# Yukari_4_Copernicus_11DoF.net
KiCad netlist of a schematic drawn in EAGLE
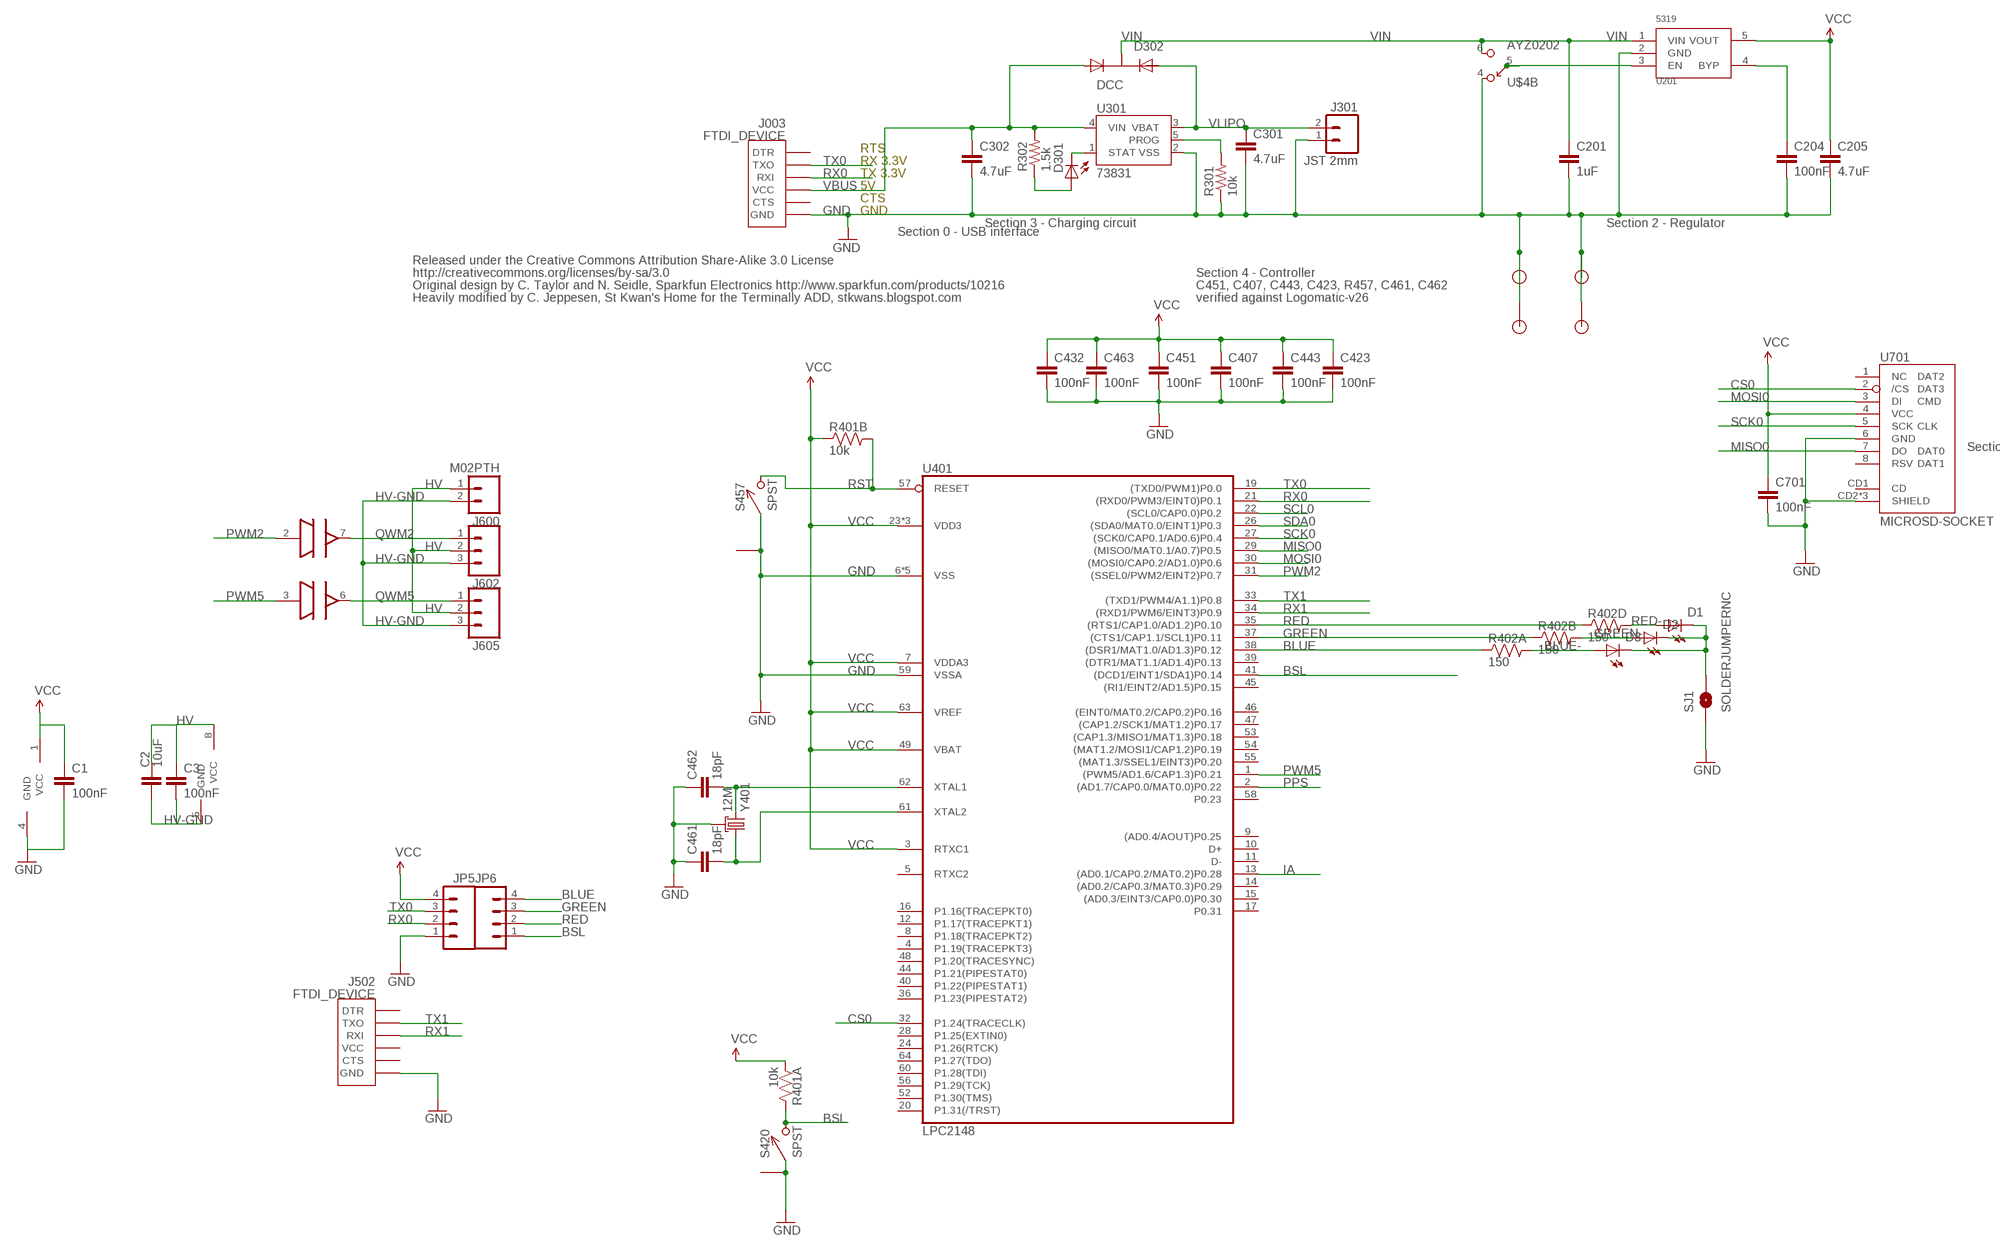
[diagram p0: schematic, sheet 1, part 1 of 2]
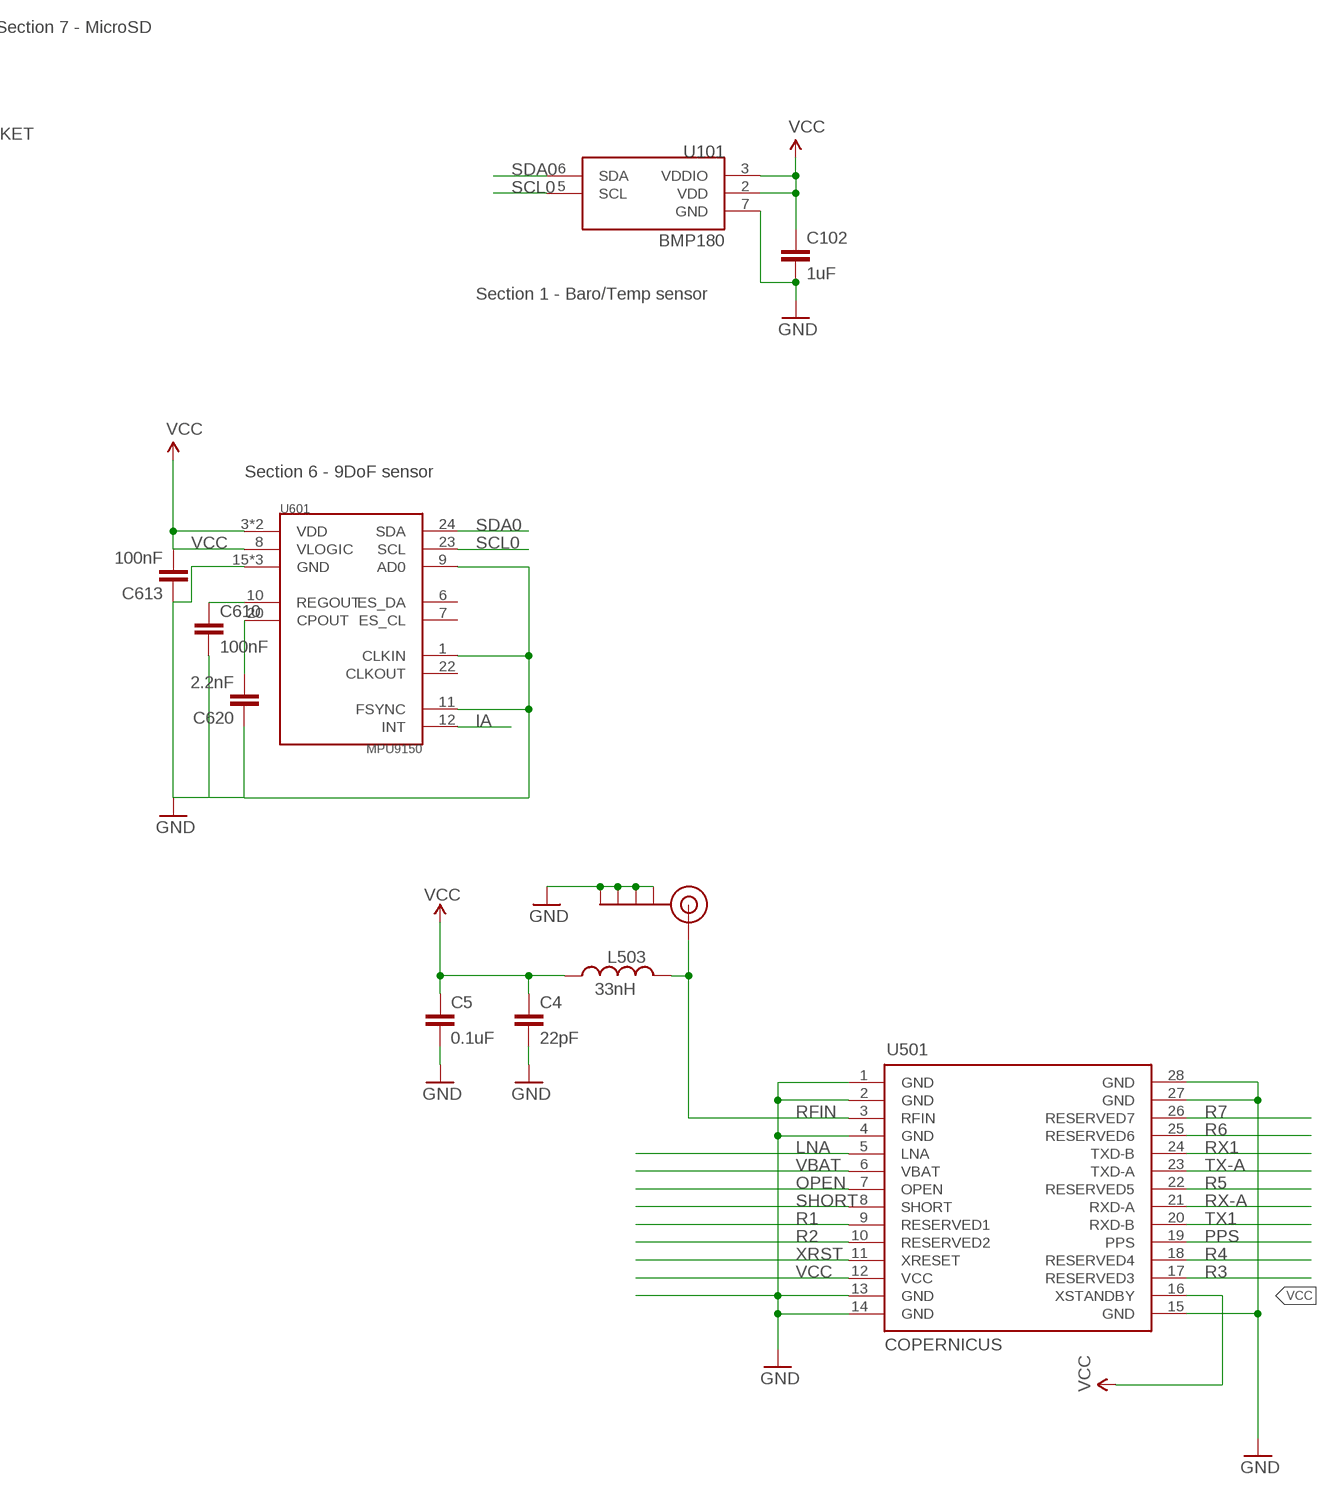
[diagram p1: schematic, sheet 1, part 2 of 2]

(export (version "E")
  (design (tool "Eeschema 10.0.6"))
  (components
    (comp (ref "C1")
      (value "100nF")
      (footprint "eagle-import:0402-CAP")
      (libsource (lib "eagle-import") (part "CAP0402-CAP"))
    )
    (comp (ref "C2")
      (value "10uF")
      (footprint "eagle-import:0603-CAP")
      (libsource (lib "eagle-import") (part "CAP0603-CAP"))
    )
    (comp (ref "C3")
      (value "100nF")
      (footprint "eagle-import:0402-CAP")
      (libsource (lib "eagle-import") (part "CAP0402-CAP"))
    )
    (comp (ref "C4")
      (value "22pF")
      (footprint "eagle-import:0603-CAP")
      (libsource (lib "eagle-import") (part "SparkFun-Passives_CAP0603-CAP"))
    )
    (comp (ref "C5")
      (value "0.1uF")
      (footprint "eagle-import:0603-CAP")
      (libsource (lib "eagle-import") (part "SparkFun-Passives_CAP0603-CAP"))
    )
    (comp (ref "C102")
      (value "1uF")
      (footprint "eagle-import:0402-CAP")
      (libsource (lib "eagle-import") (part "SparkFun-Passives_CAP0402-CAP"))
    )
    (comp (ref "C201")
      (value "1uF")
      (footprint "eagle-import:0402-CAP")
      (libsource (lib "eagle-import") (part "CAP0402-CAP"))
    )
    (comp (ref "C204")
      (value "100nF")
      (footprint "eagle-import:0402-CAP")
      (libsource (lib "eagle-import") (part "CAP0402-CAP"))
    )
    (comp (ref "C205")
      (value "4.7uF")
      (footprint "eagle-import:0402-CAP")
      (libsource (lib "eagle-import") (part "CAP0402-CAP"))
    )
    (comp (ref "C301")
      (value "4.7uF")
      (footprint "eagle-import:0402-CAP")
      (libsource (lib "eagle-import") (part "CAP0402-CAP"))
    )
    (comp (ref "C302")
      (value "4.7uF")
      (footprint "eagle-import:0402-CAP")
      (libsource (lib "eagle-import") (part "CAP0402-CAP"))
    )
    (comp (ref "C407")
      (value "100nF")
      (footprint "eagle-import:0402-CAP")
      (libsource (lib "eagle-import") (part "CAP0402-CAP"))
    )
    (comp (ref "C423")
      (value "100nF")
      (footprint "eagle-import:0402-CAP")
      (libsource (lib "eagle-import") (part "CAP0402-CAP"))
    )
    (comp (ref "C432")
      (value "100nF")
      (footprint "eagle-import:0402-CAP")
      (libsource (lib "eagle-import") (part "CAP0402-CAP"))
    )
    (comp (ref "C443")
      (value "100nF")
      (footprint "eagle-import:0402-CAP")
      (libsource (lib "eagle-import") (part "CAP0402-CAP"))
    )
    (comp (ref "C451")
      (value "100nF")
      (footprint "eagle-import:0402-CAP")
      (libsource (lib "eagle-import") (part "CAP0402-CAP"))
    )
    (comp (ref "C461")
      (value "18pF")
      (footprint "eagle-import:0402-CAP")
      (libsource (lib "eagle-import") (part "CAP0402-CAP"))
    )
    (comp (ref "C462")
      (value "18pF")
      (footprint "eagle-import:0402-CAP")
      (libsource (lib "eagle-import") (part "CAP0402-CAP"))
    )
    (comp (ref "C463")
      (value "100nF")
      (footprint "eagle-import:0402-CAP")
      (libsource (lib "eagle-import") (part "CAP0402-CAP"))
    )
    (comp (ref "C610")
      (value "100nF")
      (footprint "eagle-import:0402-CAP")
      (libsource (lib "eagle-import") (part "SparkFun-Passives_CAP0402-CAP"))
    )
    (comp (ref "C613")
      (value "100nF")
      (footprint "eagle-import:0402-CAP")
      (libsource (lib "eagle-import") (part "SparkFun-Passives_CAP0402-CAP"))
    )
    (comp (ref "C620")
      (value "2.2nF")
      (footprint "eagle-import:0402-CAP")
      (libsource (lib "eagle-import") (part "SparkFun-Passives_CAP0402-CAP"))
    )
    (comp (ref "C701")
      (value "100nF")
      (footprint "eagle-import:0402-CAP")
      (libsource (lib "eagle-import") (part "CAP0402-CAP"))
    )
    (comp (ref "D1")
      (value "RED")
      (footprint "eagle-import:LED-0603")
      (libsource (lib "eagle-import") (part "LED0603"))
    )
    (comp (ref "D2")
      (value "GREEN")
      (footprint "eagle-import:LED-0603")
      (libsource (lib "eagle-import") (part "LED0603"))
    )
    (comp (ref "D3")
      (value "BLUE")
      (footprint "eagle-import:LED-0603")
      (libsource (lib "eagle-import") (part "LED0603"))
    )
    (comp (ref "D301")
      (value "RED")
      (footprint "eagle-import:LED-0603")
      (libsource (lib "eagle-import") (part "LED0603"))
    )
    (comp (ref "D302")
      (value "DCC")
      (footprint "eagle-import:SOT-23-3")
      (libsource (lib "eagle-import") (part "PMEG2005CT"))
    )
    (comp (ref "J003")
      (value "FTDI_DEVICE")
      (footprint "eagle-import:FTDI_DEVICE_SIDE")
      (libsource (lib "eagle-import") (part "FTDI_DEVICE"))
    )
    (comp (ref "J301")
      (value "JST 2mm")
      (footprint "eagle-import:JST-2-SMD")
      (libsource (lib "eagle-import") (part "M02-JST-2MM-SMT"))
    )
    (comp (ref "J502")
      (value "FTDI_DEVICE")
      (footprint "eagle-import:FTDI_DEVICE_SIDE")
      (libsource (lib "eagle-import") (part "FTDI_DEVICE"))
    )
    (comp (ref "J600")
      (value "M02PTH")
      (footprint "eagle-import:1X02")
      (libsource (lib "eagle-import") (part "SparkFun-Connectors_M02PTH"))
    )
    (comp (ref "J602")
      (value "M03PTH")
      (footprint "eagle-import:1X03")
      (libsource (lib "eagle-import") (part "M03PTH"))
    )
    (comp (ref "J605")
      (value "M03PTH")
      (footprint "eagle-import:1X03")
      (libsource (lib "eagle-import") (part "M03PTH"))
    )
    (comp (ref "JP1")
      (value "STANDOFF")
      (footprint "eagle-import:STANDOFF")
      (libsource (lib "eagle-import") (part "STANDOFF"))
    )
    (comp (ref "JP2")
      (value "STANDOFF")
      (footprint "eagle-import:STANDOFF")
      (libsource (lib "eagle-import") (part "STANDOFF"))
    )
    (comp (ref "JP3")
      (value "STANDOFF")
      (footprint "eagle-import:STANDOFF")
      (libsource (lib "eagle-import") (part "STANDOFF"))
    )
    (comp (ref "JP4")
      (value "STANDOFF")
      (footprint "eagle-import:STANDOFF")
      (libsource (lib "eagle-import") (part "STANDOFF"))
    )
    (comp (ref "JP5")
      (value "M04PTH")
      (footprint "eagle-import:1X04")
      (libsource (lib "eagle-import") (part "M04PTH"))
    )
    (comp (ref "JP6")
      (value "M04PTH")
      (footprint "eagle-import:1X04")
      (libsource (lib "eagle-import") (part "M04PTH"))
    )
    (comp (ref "JP7")
      (value "SMA_EDGE")
      (footprint "eagle-import:SMA_EDGE")
      (libsource (lib "eagle-import") (part "SMA_EDGE"))
    )
    (comp (ref "L503")
      (value "33nH")
      (footprint "eagle-import:0603")
      (libsource (lib "eagle-import") (part "INDUCTOR0603"))
    )
    (comp (ref "R301")
      (value "10k")
      (footprint "eagle-import:0402-RES")
      (libsource (lib "eagle-import") (part "RESISTOR0402-RES"))
    )
    (comp (ref "R302")
      (value "1.5k")
      (footprint "eagle-import:0402-RES")
      (libsource (lib "eagle-import") (part "RESISTOR0402-RES"))
    )
    (comp (ref "R401")
      (value "10k")
      (footprint "eagle-import:CRA02")
      (libsource (lib "eagle-import") (part "RP2EXB24V"))
    )
    (comp (ref "R402")
      (value "150")
      (footprint "eagle-import:CRA04")
      (libsource (lib "eagle-import") (part "RP404"))
    )
    (comp (ref "S420")
      (value "SPST")
      (footprint "eagle-import:B3U-1100P")
      (libsource (lib "eagle-import") (part "B3U-1100P"))
    )
    (comp (ref "S457")
      (value "SPST")
      (footprint "eagle-import:B3U-1100P")
      (libsource (lib "eagle-import") (part "B3U-1100P"))
    )
    (comp (ref "SJ1")
      (value "SOLDERJUMPERNC")
      (footprint "eagle-import:SJ_2S")
      (libsource (lib "eagle-import") (part "SOLDERJUMPERNC"))
    )
    (comp (ref "U$4")
      (value "AYZ0202")
      (footprint "eagle-import:AYZ0202")
      (libsource (lib "eagle-import") (part "AYZ0202"))
    )
    (comp (ref "U101")
      (value "BMP180")
      (footprint "eagle-import:BMP180")
      (libsource (lib "eagle-import") (part "BMP180"))
    )
    (comp (ref "U201")
      (value "5319")
      (footprint "eagle-import:SOT-23-5")
      (libsource (lib "eagle-import") (part "MIC5319D5"))
    )
    (comp (ref "U301")
      (value "73831")
      (footprint "eagle-import:SOT23-5")
      (libsource (lib "eagle-import") (part "MCP73831"))
    )
    (comp (ref "U401")
      (value "LPC2148")
      (footprint "eagle-import:LQFP64")
      (libsource (lib "eagle-import") (part "LPC2148"))
    )
    (comp (ref "U501")
      (value "COPERNICUS")
      (footprint "eagle-import:COPERNICUS")
      (libsource (lib "eagle-import") (part "COPERNICUSSMD"))
    )
    (comp (ref "U600")
      (value "ADUM3221")
      (footprint "eagle-import:SO8N")
      (libsource (lib "eagle-import") (part "ADUM3221"))
    )
    (comp (ref "U601")
      (value "MPU9150")
      (footprint "eagle-import:LLGA24")
      (libsource (lib "eagle-import") (part "MPU9150"))
    )
    (comp (ref "U701")
      (value "MICROSD-SOCKET")
      (footprint "eagle-import:MICROSD-SOCKET-PP")
      (libsource (lib "eagle-import") (part "MICROSD-SOCKET"))
    )
    (comp (ref "Y401")
      (value "12M")
      (footprint "eagle-import:CRYSTAL_SMD")
      (libsource (lib "eagle-import") (part "TSX-3225"))
    )
  )
  (nets
    (net (code "1") (name "/BLUE") (class "Default")
      (node (ref "JP6") (pin "4") (pinfunction "4_4") (pintype "passive"))
      (node (ref "R402") (pin "1") (pinfunction "1_1") (pintype "passive"))
      (node (ref "U401") (pin "38") (pinfunction "(DSR1/MAT1.0/AD1.3)P0.12_38") (pintype "bidirectional"))
    )
    (net (code "2") (name "/BLUE-") (class "Default")
      (node (ref "D3") (pin "A") (pinfunction "A_A") (pintype "passive"))
      (node (ref "R402") (pin "8") (pinfunction "2_8") (pintype "passive"))
    )
    (net (code "3") (name "/BSL") (class "Default")
      (node (ref "JP6") (pin "1") (pinfunction "1_1") (pintype "passive"))
      (node (ref "R401") (pin "4") (pinfunction "2_4") (pintype "passive"))
      (node (ref "S420") (pin "P$2") (pinfunction "2_P$2") (pintype "bidirectional"))
      (node (ref "U401") (pin "41") (pinfunction "(DCD1/EINT1/SDA1)P0.14_41") (pintype "bidirectional"))
    )
    (net (code "4") (name "/CS0") (class "Default")
      (node (ref "U401") (pin "32") (pinfunction "P1.24(TRACECLK)_32") (pintype "bidirectional"))
      (node (ref "U701") (pin "2") (pinfunction "/CS_2") (pintype "bidirectional"))
    )
    (net (code "5") (name "/GREEN") (class "Default")
      (node (ref "JP6") (pin "3") (pinfunction "3_3") (pintype "passive"))
      (node (ref "R402") (pin "2") (pinfunction "1_2") (pintype "passive"))
      (node (ref "U401") (pin "37") (pinfunction "(CTS1/CAP1.1/SCL1)P0.11_37") (pintype "bidirectional"))
    )
    (net (code "6") (name "/GREEN-") (class "Default")
      (node (ref "D2") (pin "A") (pinfunction "A_A") (pintype "passive"))
      (node (ref "R402") (pin "7") (pinfunction "2_7") (pintype "passive"))
    )
    (net (code "7") (name "/HV") (class "Default")
      (node (ref "C2") (pin "1") (pinfunction "1_1") (pintype "passive"))
      (node (ref "C3") (pin "1") (pinfunction "1_1") (pintype "passive"))
      (node (ref "J600") (pin "1") (pinfunction "1_1") (pintype "passive"))
      (node (ref "J602") (pin "2") (pinfunction "2_2") (pintype "passive"))
      (node (ref "J605") (pin "2") (pinfunction "2_2") (pintype "passive"))
      (node (ref "U600") (pin "8") (pinfunction "VCC_8") (pintype "bidirectional"))
    )
    (net (code "8") (name "/HV-GND") (class "Default")
      (node (ref "C2") (pin "2") (pinfunction "2_2") (pintype "passive"))
      (node (ref "C3") (pin "2") (pinfunction "2_2") (pintype "passive"))
      (node (ref "J600") (pin "2") (pinfunction "2_2") (pintype "passive"))
      (node (ref "J602") (pin "3") (pinfunction "3_3") (pintype "passive"))
      (node (ref "J605") (pin "3") (pinfunction "3_3") (pintype "passive"))
      (node (ref "U600") (pin "5") (pinfunction "GND_5") (pintype "bidirectional"))
    )
    (net (code "9") (name "/IA") (class "Default")
      (node (ref "U401") (pin "13") (pinfunction "(AD0.1/CAP0.2/MAT0.2)P0.28_13") (pintype "bidirectional"))
      (node (ref "U601") (pin "12") (pinfunction "INT_12") (pintype "bidirectional"))
    )
    (net (code "10") (name "/LNA") (class "Default")
      (node (ref "U501") (pin "5") (pinfunction "LNA_5") (pintype "bidirectional"))
    )
    (net (code "11") (name "/MISO0") (class "Default")
      (node (ref "U401") (pin "29") (pinfunction "(MISO0/MAT0.1/A0.7)P0.5_29") (pintype "bidirectional"))
      (node (ref "U701") (pin "7") (pinfunction "DO_7") (pintype "bidirectional"))
    )
    (net (code "12") (name "/MOSI0") (class "Default")
      (node (ref "U401") (pin "30") (pinfunction "(MOSI0/CAP0.2/AD1.0)P0.6_30") (pintype "bidirectional"))
      (node (ref "U701") (pin "3") (pinfunction "DI_3") (pintype "bidirectional"))
    )
    (net (code "13") (name "/OPEN") (class "Default")
      (node (ref "U501") (pin "7") (pinfunction "OPEN_7") (pintype "bidirectional"))
    )
    (net (code "14") (name "/PPS") (class "Default")
      (node (ref "U401") (pin "2") (pinfunction "(AD1.7/CAP0.0/MAT0.0)P0.22_2") (pintype "bidirectional"))
      (node (ref "U501") (pin "19") (pinfunction "PPS_19") (pintype "bidirectional"))
    )
    (net (code "15") (name "/PWM2") (class "Default")
      (node (ref "U401") (pin "31") (pinfunction "(SSEL0/PWM2/EINT2)P0.7_31") (pintype "bidirectional"))
      (node (ref "U600") (pin "2") (pinfunction "IN_2") (pintype "input"))
    )
    (net (code "16") (name "/PWM5") (class "Default")
      (node (ref "U401") (pin "1") (pinfunction "(PWM5/AD1.6/CAP1.3)P0.21_1") (pintype "bidirectional"))
      (node (ref "U600") (pin "3") (pinfunction "IN_3") (pintype "input"))
    )
    (net (code "17") (name "/QWM2") (class "Default")
      (node (ref "J602") (pin "1") (pinfunction "1_1") (pintype "passive"))
      (node (ref "U600") (pin "7") (pinfunction "OUT_7") (pintype "bidirectional"))
    )
    (net (code "18") (name "/QWM5") (class "Default")
      (node (ref "J605") (pin "1") (pinfunction "1_1") (pintype "passive"))
      (node (ref "U600") (pin "6") (pinfunction "OUT_6") (pintype "bidirectional"))
    )
    (net (code "19") (name "/R1") (class "Default")
      (node (ref "U501") (pin "9") (pinfunction "RESERVED1_9") (pintype "bidirectional"))
    )
    (net (code "20") (name "/R2") (class "Default")
      (node (ref "U501") (pin "10") (pinfunction "RESERVED2_10") (pintype "bidirectional"))
    )
    (net (code "21") (name "/R3") (class "Default")
      (node (ref "U501") (pin "17") (pinfunction "RESERVED3_17") (pintype "bidirectional"))
    )
    (net (code "22") (name "/R4") (class "Default")
      (node (ref "U501") (pin "18") (pinfunction "RESERVED4_18") (pintype "bidirectional"))
    )
    (net (code "23") (name "/R5") (class "Default")
      (node (ref "U501") (pin "22") (pinfunction "RESERVED5_22") (pintype "bidirectional"))
    )
    (net (code "24") (name "/R6") (class "Default")
      (node (ref "U501") (pin "25") (pinfunction "RESERVED6_25") (pintype "bidirectional"))
    )
    (net (code "25") (name "/R7") (class "Default")
      (node (ref "U501") (pin "26") (pinfunction "RESERVED7_26") (pintype "bidirectional"))
    )
    (net (code "26") (name "/RED") (class "Default")
      (node (ref "JP6") (pin "2") (pinfunction "2_2") (pintype "passive"))
      (node (ref "R402") (pin "4") (pinfunction "1_4") (pintype "passive"))
      (node (ref "U401") (pin "35") (pinfunction "(RTS1/CAP1.0/AD1.2)P0.10_35") (pintype "bidirectional"))
    )
    (net (code "27") (name "/RED-") (class "Default")
      (node (ref "D1") (pin "A") (pinfunction "A_A") (pintype "passive"))
      (node (ref "R402") (pin "5") (pinfunction "2_5") (pintype "passive"))
    )
    (net (code "28") (name "/RFIN") (class "Default")
      (node (ref "JP7") (pin "SIG") (pinfunction "SIGNAL_SIG") (pintype "bidirectional"))
      (node (ref "L503") (pin "2") (pinfunction "2_2") (pintype "passive"))
      (node (ref "U501") (pin "3") (pinfunction "RFIN_3") (pintype "bidirectional"))
    )
    (net (code "29") (name "/RST") (class "Default")
      (node (ref "R401") (pin "3") (pinfunction "2_3") (pintype "passive"))
      (node (ref "S457") (pin "P$2") (pinfunction "2_P$2") (pintype "bidirectional"))
      (node (ref "U401") (pin "57") (pinfunction "RESET_57") (pintype "input"))
    )
    (net (code "30") (name "/RX-A") (class "Default")
      (node (ref "U501") (pin "21") (pinfunction "RXD-A_21") (pintype "bidirectional"))
    )
    (net (code "31") (name "/RX0") (class "Default")
      (node (ref "J003") (pin "P$3") (pinfunction "RXI_P$3") (pintype "bidirectional"))
      (node (ref "JP5") (pin "2") (pinfunction "2_2") (pintype "passive"))
      (node (ref "U401") (pin "21") (pinfunction "(RXD0/PWM3/EINT0)P0.1_21") (pintype "bidirectional"))
    )
    (net (code "32") (name "/RX1") (class "Default")
      (node (ref "J502") (pin "P$3") (pinfunction "RXI_P$3") (pintype "bidirectional"))
      (node (ref "U401") (pin "34") (pinfunction "(RXD1/PWM6/EINT3)P0.9_34") (pintype "bidirectional"))
      (node (ref "U501") (pin "24") (pinfunction "TXD-B_24") (pintype "bidirectional"))
    )
    (net (code "33") (name "/SCK0") (class "Default")
      (node (ref "U401") (pin "27") (pinfunction "(SCK0/CAP0.1/AD0.6)P0.4_27") (pintype "bidirectional"))
      (node (ref "U701") (pin "5") (pinfunction "SCK_5") (pintype "bidirectional"))
    )
    (net (code "34") (name "/SCL0") (class "Default")
      (node (ref "U101") (pin "5") (pinfunction "SCL_5") (pintype "input"))
      (node (ref "U401") (pin "22") (pinfunction "(SCL0/CAP0.0)P0.2_22") (pintype "bidirectional"))
      (node (ref "U601") (pin "23") (pinfunction "SCL_23") (pintype "bidirectional"))
    )
    (net (code "35") (name "/SDA0") (class "Default")
      (node (ref "U101") (pin "6") (pinfunction "SDA_6") (pintype "bidirectional"))
      (node (ref "U401") (pin "26") (pinfunction "(SDA0/MAT0.0/EINT1)P0.3_26") (pintype "bidirectional"))
      (node (ref "U601") (pin "24") (pinfunction "SDA_24") (pintype "bidirectional"))
    )
    (net (code "36") (name "/SHORT") (class "Default")
      (node (ref "U501") (pin "8") (pinfunction "SHORT_8") (pintype "bidirectional"))
    )
    (net (code "37") (name "/TX-A") (class "Default")
      (node (ref "U501") (pin "23") (pinfunction "TXD-A_23") (pintype "bidirectional"))
    )
    (net (code "38") (name "/TX0") (class "Default")
      (node (ref "J003") (pin "P$2") (pinfunction "TXO_P$2") (pintype "bidirectional"))
      (node (ref "JP5") (pin "3") (pinfunction "3_3") (pintype "passive"))
      (node (ref "U401") (pin "19") (pinfunction "(TXD0/PWM1)P0.0_19") (pintype "bidirectional"))
    )
    (net (code "39") (name "/TX1") (class "Default")
      (node (ref "J502") (pin "P$2") (pinfunction "TXO_P$2") (pintype "bidirectional"))
      (node (ref "U401") (pin "33") (pinfunction "(TXD1/PWM4/A1.1)P0.8_33") (pintype "bidirectional"))
      (node (ref "U501") (pin "20") (pinfunction "RXD-B_20") (pintype "bidirectional"))
    )
    (net (code "40") (name "/VBAT") (class "Default")
      (node (ref "U501") (pin "6") (pinfunction "VBAT_6") (pintype "bidirectional"))
    )
    (net (code "41") (name "/VBUS") (class "Default")
      (node (ref "C302") (pin "1") (pinfunction "1_1") (pintype "passive"))
      (node (ref "D302") (pin "1") (pinfunction "A1_1") (pintype "passive"))
      (node (ref "J003") (pin "P$4") (pinfunction "VCC_P$4") (pintype "bidirectional"))
      (node (ref "R302") (pin "2") (pinfunction "2_2") (pintype "passive"))
      (node (ref "U301") (pin "4") (pinfunction "VIN_4") (pintype "power_in"))
    )
    (net (code "42") (name "/VIN") (class "Default")
      (node (ref "C201") (pin "1") (pinfunction "1_1") (pintype "passive"))
      (node (ref "D302") (pin "3") (pinfunction "K_3") (pintype "passive"))
      (node (ref "U$4") (pin "6") (pinfunction "P$2_6") (pintype "bidirectional"))
      (node (ref "U201") (pin "1") (pinfunction "VIN_1") (pintype "bidirectional"))
    )
    (net (code "43") (name "/VLIPO") (class "Default")
      (node (ref "C301") (pin "1") (pinfunction "1_1") (pintype "passive"))
      (node (ref "D302") (pin "2") (pinfunction "A2_2") (pintype "passive"))
      (node (ref "J301") (pin "2") (pinfunction "2_2") (pintype "passive"))
      (node (ref "U301") (pin "3") (pinfunction "VBAT_3") (pintype "power_in"))
    )
    (net (code "44") (name "/XRST") (class "Default")
      (node (ref "U501") (pin "11") (pinfunction "XRESET_11") (pintype "bidirectional"))
    )
    (net (code "45") (name "GND") (class "Default")
      (node (ref "C1") (pin "2") (pinfunction "2_2") (pintype "passive"))
      (node (ref "C102") (pin "2") (pinfunction "2_2") (pintype "passive"))
      (node (ref "C201") (pin "2") (pinfunction "2_2") (pintype "passive"))
      (node (ref "C204") (pin "2") (pinfunction "2_2") (pintype "passive"))
      (node (ref "C205") (pin "2") (pinfunction "2_2") (pintype "passive"))
      (node (ref "C301") (pin "2") (pinfunction "2_2") (pintype "passive"))
      (node (ref "C302") (pin "2") (pinfunction "2_2") (pintype "passive"))
      (node (ref "C4") (pin "2") (pinfunction "2_2") (pintype "passive"))
      (node (ref "C407") (pin "2") (pinfunction "2_2") (pintype "passive"))
      (node (ref "C423") (pin "2") (pinfunction "2_2") (pintype "passive"))
      (node (ref "C432") (pin "2") (pinfunction "2_2") (pintype "passive"))
      (node (ref "C443") (pin "2") (pinfunction "2_2") (pintype "passive"))
      (node (ref "C451") (pin "2") (pinfunction "2_2") (pintype "passive"))
      (node (ref "C461") (pin "1") (pinfunction "1_1") (pintype "passive"))
      (node (ref "C462") (pin "1") (pinfunction "1_1") (pintype "passive"))
      (node (ref "C463") (pin "2") (pinfunction "2_2") (pintype "passive"))
      (node (ref "C5") (pin "2") (pinfunction "2_2") (pintype "passive"))
      (node (ref "C610") (pin "2") (pinfunction "2_2") (pintype "passive"))
      (node (ref "C613") (pin "1") (pinfunction "1_1") (pintype "passive"))
      (node (ref "C620") (pin "1") (pinfunction "1_1") (pintype "passive"))
      (node (ref "C701") (pin "2") (pinfunction "2_2") (pintype "passive"))
      (node (ref "J003") (pin "P$6") (pinfunction "GND_P$6") (pintype "bidirectional"))
      (node (ref "J301") (pin "1") (pinfunction "1_1") (pintype "passive"))
      (node (ref "J502") (pin "P$6") (pinfunction "GND_P$6") (pintype "bidirectional"))
      (node (ref "JP1") (pin "P$1") (pinfunction "P$1_P$1") (pintype "bidirectional"))
      (node (ref "JP2") (pin "P$1") (pinfunction "P$1_P$1") (pintype "bidirectional"))
      (node (ref "JP3") (pin "P$1") (pinfunction "P$1_P$1") (pintype "bidirectional"))
      (node (ref "JP4") (pin "P$1") (pinfunction "P$1_P$1") (pintype "bidirectional"))
      (node (ref "JP5") (pin "1") (pinfunction "1_1") (pintype "passive"))
      (node (ref "JP7") (pin "GND@0") (pinfunction "GND_GND@0") (pintype "bidirectional"))
      (node (ref "JP7") (pin "GND@1") (pinfunction "GND_GND@1") (pintype "bidirectional"))
      (node (ref "JP7") (pin "GND@2") (pinfunction "GND_GND@2") (pintype "bidirectional"))
      (node (ref "JP7") (pin "GND@3") (pinfunction "GND_GND@3") (pintype "bidirectional"))
      (node (ref "R301") (pin "1") (pinfunction "1_1") (pintype "passive"))
      (node (ref "S420") (pin "P$1") (pinfunction "1_P$1") (pintype "bidirectional"))
      (node (ref "S420") (pin "P$3") (pinfunction "1_P$3") (pintype "bidirectional"))
      (node (ref "S457") (pin "P$1") (pinfunction "1_P$1") (pintype "bidirectional"))
      (node (ref "S457") (pin "P$3") (pinfunction "1_P$3") (pintype "bidirectional"))
      (node (ref "SJ1") (pin "1") (pinfunction "1_1") (pintype "passive"))
      (node (ref "U$4") (pin "4") (pinfunction "P$1_4") (pintype "bidirectional"))
      (node (ref "U101") (pin "7") (pinfunction "GND_7") (pintype "power_in"))
      (node (ref "U201") (pin "2") (pinfunction "GND_2") (pintype "bidirectional"))
      (node (ref "U301") (pin "2") (pinfunction "VSS_2") (pintype "power_in"))
      (node (ref "U401") (pin "18") (pinfunction "VSS_18") (pintype "power_in"))
      (node (ref "U401") (pin "25") (pinfunction "VSS_25") (pintype "power_in"))
      (node (ref "U401") (pin "42") (pinfunction "VSS_42") (pintype "power_in"))
      (node (ref "U401") (pin "50") (pinfunction "VSS_50") (pintype "power_in"))
      (node (ref "U401") (pin "59") (pinfunction "VSSA_59") (pintype "power_in"))
      (node (ref "U401") (pin "6") (pinfunction "VSS_6") (pintype "power_in"))
      (node (ref "U501") (pin "1") (pinfunction "GND_1") (pintype "bidirectional"))
      (node (ref "U501") (pin "13") (pinfunction "GND_13") (pintype "bidirectional"))
      (node (ref "U501") (pin "14") (pinfunction "GND_14") (pintype "bidirectional"))
      (node (ref "U501") (pin "15") (pinfunction "GND_15") (pintype "bidirectional"))
      (node (ref "U501") (pin "2") (pinfunction "GND_2") (pintype "bidirectional"))
      (node (ref "U501") (pin "27") (pinfunction "GND_27") (pintype "bidirectional"))
      (node (ref "U501") (pin "28") (pinfunction "GND_28") (pintype "bidirectional"))
      (node (ref "U501") (pin "4") (pinfunction "GND_4") (pintype "bidirectional"))
      (node (ref "U600") (pin "4") (pinfunction "GND_4") (pintype "bidirectional"))
      (node (ref "U601") (pin "1") (pinfunction "CLKIN_1") (pintype "bidirectional"))
      (node (ref "U601") (pin "11") (pinfunction "FSYNC_11") (pintype "bidirectional"))
      (node (ref "U601") (pin "15") (pinfunction "GND_15") (pintype "bidirectional"))
      (node (ref "U601") (pin "17") (pinfunction "GND_17") (pintype "bidirectional"))
      (node (ref "U601") (pin "18") (pinfunction "GND_18") (pintype "bidirectional"))
      (node (ref "U601") (pin "9") (pinfunction "AD0_9") (pintype "bidirectional"))
      (node (ref "U701") (pin "6") (pinfunction "GND_6") (pintype "bidirectional"))
      (node (ref "U701") (pin "CD2") (pinfunction "SHIELD_CD2") (pintype "bidirectional"))
      (node (ref "U701") (pin "GND1") (pinfunction "SHIELD_GND1") (pintype "bidirectional"))
      (node (ref "U701") (pin "GND3") (pinfunction "SHIELD_GND3") (pintype "bidirectional"))
      (node (ref "Y401") (pin "2") (pinfunction "GND_2") (pintype "passive"))
      (node (ref "Y401") (pin "4") (pinfunction "GND_4") (pintype "passive"))
    )
    (net (code "46") (name "Net-(D1-PadC)") (class "Default")
      (node (ref "D1") (pin "C") (pinfunction "C_C") (pintype "passive"))
      (node (ref "D2") (pin "C") (pinfunction "C_C") (pintype "passive"))
      (node (ref "D3") (pin "C") (pinfunction "C_C") (pintype "passive"))
      (node (ref "SJ1") (pin "2") (pinfunction "2_2") (pintype "passive"))
    )
    (net (code "47") (name "Net-(D301-PadA)") (class "Default")
      (node (ref "D301") (pin "A") (pinfunction "A_A") (pintype "passive"))
      (node (ref "R302") (pin "1") (pinfunction "1_1") (pintype "passive"))
    )
    (net (code "48") (name "Net-(U$4B-P$3)") (class "Default")
      (node (ref "U$4") (pin "5") (pinfunction "P$3_5") (pintype "bidirectional"))
      (node (ref "U201") (pin "3") (pinfunction "EN_3") (pintype "bidirectional"))
    )
    (net (code "49") (name "Net-(U201-BYP)") (class "Default")
      (node (ref "C204") (pin "1") (pinfunction "1_1") (pintype "passive"))
      (node (ref "U201") (pin "4") (pinfunction "BYP_4") (pintype "bidirectional"))
    )
    (net (code "50") (name "Net-(U301-PROG)") (class "Default")
      (node (ref "R301") (pin "2") (pinfunction "2_2") (pintype "passive"))
      (node (ref "U301") (pin "5") (pinfunction "PROG_5") (pintype "input"))
    )
    (net (code "51") (name "Net-(U301-STAT)") (class "Default")
      (node (ref "D301") (pin "C") (pinfunction "C_C") (pintype "passive"))
      (node (ref "U301") (pin "1") (pinfunction "STAT_1") (pintype "output"))
    )
    (net (code "52") (name "Net-(U401-XTAL1)") (class "Default")
      (node (ref "C462") (pin "2") (pinfunction "2_2") (pintype "passive"))
      (node (ref "U401") (pin "62") (pinfunction "XTAL1_62") (pintype "input"))
      (node (ref "Y401") (pin "3") (pinfunction "2_3") (pintype "passive"))
    )
    (net (code "53") (name "Net-(U401-XTAL2)") (class "Default")
      (node (ref "C461") (pin "2") (pinfunction "2_2") (pintype "passive"))
      (node (ref "U401") (pin "61") (pinfunction "XTAL2_61") (pintype "output"))
      (node (ref "Y401") (pin "1") (pinfunction "1_1") (pintype "passive"))
    )
    (net (code "54") (name "Net-(U601-CPOUT)") (class "Default")
      (node (ref "C620") (pin "2") (pinfunction "2_2") (pintype "passive"))
      (node (ref "U601") (pin "20") (pinfunction "CPOUT_20") (pintype "bidirectional"))
    )
    (net (code "55") (name "Net-(U601-REGOUT)") (class "Default")
      (node (ref "C610") (pin "1") (pinfunction "1_1") (pintype "passive"))
      (node (ref "U601") (pin "10") (pinfunction "REGOUT_10") (pintype "bidirectional"))
    )
    (net (code "56") (name "VCC") (class "Default")
      (node (ref "C1") (pin "1") (pinfunction "1_1") (pintype "passive"))
      (node (ref "C102") (pin "1") (pinfunction "1_1") (pintype "passive"))
      (node (ref "C205") (pin "1") (pinfunction "1_1") (pintype "passive"))
      (node (ref "C4") (pin "1") (pinfunction "1_1") (pintype "passive"))
      (node (ref "C407") (pin "1") (pinfunction "1_1") (pintype "passive"))
      (node (ref "C423") (pin "1") (pinfunction "1_1") (pintype "passive"))
      (node (ref "C432") (pin "1") (pinfunction "1_1") (pintype "passive"))
      (node (ref "C443") (pin "1") (pinfunction "1_1") (pintype "passive"))
      (node (ref "C451") (pin "1") (pinfunction "1_1") (pintype "passive"))
      (node (ref "C463") (pin "1") (pinfunction "1_1") (pintype "passive"))
      (node (ref "C5") (pin "1") (pinfunction "1_1") (pintype "passive"))
      (node (ref "C613") (pin "2") (pinfunction "2_2") (pintype "passive"))
      (node (ref "C701") (pin "1") (pinfunction "1_1") (pintype "passive"))
      (node (ref "JP5") (pin "4") (pinfunction "4_4") (pintype "passive"))
      (node (ref "L503") (pin "1") (pinfunction "1_1") (pintype "passive"))
      (node (ref "R401") (pin "1") (pinfunction "1_1") (pintype "passive"))
      (node (ref "R401") (pin "2") (pinfunction "1_2") (pintype "passive"))
      (node (ref "U101") (pin "2") (pinfunction "VDD_2") (pintype "power_in"))
      (node (ref "U101") (pin "3") (pinfunction "VDDIO_3") (pintype "power_in"))
      (node (ref "U201") (pin "5") (pinfunction "VOUT_5") (pintype "bidirectional"))
      (node (ref "U401") (pin "23") (pinfunction "VDD3_23") (pintype "power_in"))
      (node (ref "U401") (pin "3") (pinfunction "RTXC1_3") (pintype "input"))
      (node (ref "U401") (pin "43") (pinfunction "VDD3_43") (pintype "power_in"))
      (node (ref "U401") (pin "49") (pinfunction "VBAT_49") (pintype "power_in"))
      (node (ref "U401") (pin "51") (pinfunction "VDD3_51") (pintype "power_in"))
      (node (ref "U401") (pin "63") (pinfunction "VREF_63") (pintype "input"))
      (node (ref "U401") (pin "7") (pinfunction "VDDA3_7") (pintype "power_in"))
      (node (ref "U501") (pin "12") (pinfunction "VCC_12") (pintype "bidirectional"))
      (node (ref "U501") (pin "16") (pinfunction "XSTANDBY_16") (pintype "bidirectional"))
      (node (ref "U600") (pin "1") (pinfunction "VCC_1") (pintype "bidirectional"))
      (node (ref "U601") (pin "13") (pinfunction "VDD_13") (pintype "bidirectional"))
      (node (ref "U601") (pin "3") (pinfunction "VDD_3") (pintype "bidirectional"))
      (node (ref "U601") (pin "8") (pinfunction "VLOGIC_8") (pintype "bidirectional"))
      (node (ref "U701") (pin "4") (pinfunction "VCC_4") (pintype "bidirectional"))
    )
    (net (code "57") (name "unconnected-(J003-CTS-PadP$5)") (class "Default")
      (node (ref "J003") (pin "P$5") (pinfunction "CTS_P$5") (pintype "bidirectional"))
    )
    (net (code "58") (name "unconnected-(J003-DTR-PadP$1)") (class "Default")
      (node (ref "J003") (pin "P$1") (pinfunction "DTR_P$1") (pintype "bidirectional"))
    )
    (net (code "59") (name "unconnected-(J502-CTS-PadP$5)") (class "Default")
      (node (ref "J502") (pin "P$5") (pinfunction "CTS_P$5") (pintype "bidirectional"))
    )
    (net (code "60") (name "unconnected-(J502-DTR-PadP$1)") (class "Default")
      (node (ref "J502") (pin "P$1") (pinfunction "DTR_P$1") (pintype "bidirectional"))
    )
    (net (code "61") (name "unconnected-(J502-VCC-PadP$4)") (class "Default")
      (node (ref "J502") (pin "P$4") (pinfunction "VCC_P$4") (pintype "bidirectional"))
    )
    (net (code "62") (name "unconnected-(U401-(AD0.2{slash}CAP0.3{slash}MAT0.3)P0.29-Pad14)") (class "Default")
      (node (ref "U401") (pin "14") (pinfunction "(AD0.2/CAP0.3/MAT0.3)P0.29_14") (pintype "bidirectional"))
    )
    (net (code "63") (name "unconnected-(U401-(AD0.3{slash}EINT3{slash}CAP0.0)P0.30-Pad15)") (class "Default")
      (node (ref "U401") (pin "15") (pinfunction "(AD0.3/EINT3/CAP0.0)P0.30_15") (pintype "bidirectional"))
    )
    (net (code "64") (name "unconnected-(U401-(AD0.4{slash}AOUT)P0.25-Pad9)") (class "Default")
      (node (ref "U401") (pin "9") (pinfunction "(AD0.4/AOUT)P0.25_9") (pintype "bidirectional"))
    )
    (net (code "65") (name "unconnected-(U401-(CAP1.2{slash}SCK1{slash}MAT1.2)P0.17-Pad47)") (class "Default")
      (node (ref "U401") (pin "47") (pinfunction "(CAP1.2/SCK1/MAT1.2)P0.17_47") (pintype "bidirectional"))
    )
    (net (code "66") (name "unconnected-(U401-(CAP1.3{slash}MISO1{slash}MAT1.3)P0.18-Pad53)") (class "Default")
      (node (ref "U401") (pin "53") (pinfunction "(CAP1.3/MISO1/MAT1.3)P0.18_53") (pintype "bidirectional"))
    )
    (net (code "67") (name "unconnected-(U401-(DTR1{slash}MAT1.1{slash}AD1.4)P0.13-Pad39)") (class "Default")
      (node (ref "U401") (pin "39") (pinfunction "(DTR1/MAT1.1/AD1.4)P0.13_39") (pintype "bidirectional"))
    )
    (net (code "68") (name "unconnected-(U401-(EINT0{slash}MAT0.2{slash}CAP0.2)P0.16-Pad46)") (class "Default")
      (node (ref "U401") (pin "46") (pinfunction "(EINT0/MAT0.2/CAP0.2)P0.16_46") (pintype "bidirectional"))
    )
    (net (code "69") (name "unconnected-(U401-(MAT1.2{slash}MOSI1{slash}CAP1.2)P0.19-Pad54)") (class "Default")
      (node (ref "U401") (pin "54") (pinfunction "(MAT1.2/MOSI1/CAP1.2)P0.19_54") (pintype "bidirectional"))
    )
    (net (code "70") (name "unconnected-(U401-(MAT1.3{slash}SSEL1{slash}EINT3)P0.20-Pad55)") (class "Default")
      (node (ref "U401") (pin "55") (pinfunction "(MAT1.3/SSEL1/EINT3)P0.20_55") (pintype "bidirectional"))
    )
    (net (code "71") (name "unconnected-(U401-(RI1{slash}EINT2{slash}AD1.5)P0.15-Pad45)") (class "Default")
      (node (ref "U401") (pin "45") (pinfunction "(RI1/EINT2/AD1.5)P0.15_45") (pintype "bidirectional"))
    )
    (net (code "72") (name "unconnected-(U401-D+-Pad10)") (class "Default")
      (node (ref "U401") (pin "10") (pinfunction "D+_10") (pintype "bidirectional"))
    )
    (net (code "73") (name "unconnected-(U401-D--Pad11)") (class "Default")
      (node (ref "U401") (pin "11") (pinfunction "D-_11") (pintype "bidirectional"))
    )
    (net (code "74") (name "unconnected-(U401-P0.23-Pad58)") (class "Default")
      (node (ref "U401") (pin "58") (pinfunction "P0.23_58") (pintype "bidirectional"))
    )
    (net (code "75") (name "unconnected-(U401-P0.31-Pad17)") (class "Default")
      (node (ref "U401") (pin "17") (pinfunction "P0.31_17") (pintype "output"))
    )
    (net (code "76") (name "unconnected-(U401-P1.16(TRACEPKT0)-Pad16)") (class "Default")
      (node (ref "U401") (pin "16") (pinfunction "P1.16(TRACEPKT0)_16") (pintype "bidirectional"))
    )
    (net (code "77") (name "unconnected-(U401-P1.17(TRACEPKT1)-Pad12)") (class "Default")
      (node (ref "U401") (pin "12") (pinfunction "P1.17(TRACEPKT1)_12") (pintype "bidirectional"))
    )
    (net (code "78") (name "unconnected-(U401-P1.18(TRACEPKT2)-Pad8)") (class "Default")
      (node (ref "U401") (pin "8") (pinfunction "P1.18(TRACEPKT2)_8") (pintype "bidirectional"))
    )
    (net (code "79") (name "unconnected-(U401-P1.19(TRACEPKT3)-Pad4)") (class "Default")
      (node (ref "U401") (pin "4") (pinfunction "P1.19(TRACEPKT3)_4") (pintype "bidirectional"))
    )
    (net (code "80") (name "unconnected-(U401-P1.20(TRACESYNC)-Pad48)") (class "Default")
      (node (ref "U401") (pin "48") (pinfunction "P1.20(TRACESYNC)_48") (pintype "bidirectional"))
    )
    (net (code "81") (name "unconnected-(U401-P1.21(PIPESTAT0)-Pad44)") (class "Default")
      (node (ref "U401") (pin "44") (pinfunction "P1.21(PIPESTAT0)_44") (pintype "bidirectional"))
    )
    (net (code "82") (name "unconnected-(U401-P1.22(PIPESTAT1)-Pad40)") (class "Default")
      (node (ref "U401") (pin "40") (pinfunction "P1.22(PIPESTAT1)_40") (pintype "bidirectional"))
    )
    (net (code "83") (name "unconnected-(U401-P1.23(PIPESTAT2)-Pad36)") (class "Default")
      (node (ref "U401") (pin "36") (pinfunction "P1.23(PIPESTAT2)_36") (pintype "bidirectional"))
    )
    (net (code "84") (name "unconnected-(U401-P1.25(EXTIN0)-Pad28)") (class "Default")
      (node (ref "U401") (pin "28") (pinfunction "P1.25(EXTIN0)_28") (pintype "bidirectional"))
    )
    (net (code "85") (name "unconnected-(U401-P1.26(RTCK)-Pad24)") (class "Default")
      (node (ref "U401") (pin "24") (pinfunction "P1.26(RTCK)_24") (pintype "bidirectional"))
    )
    (net (code "86") (name "unconnected-(U401-P1.27(TDO)-Pad64)") (class "Default")
      (node (ref "U401") (pin "64") (pinfunction "P1.27(TDO)_64") (pintype "bidirectional"))
    )
    (net (code "87") (name "unconnected-(U401-P1.28(TDI)-Pad60)") (class "Default")
      (node (ref "U401") (pin "60") (pinfunction "P1.28(TDI)_60") (pintype "bidirectional"))
    )
    (net (code "88") (name "unconnected-(U401-P1.29(TCK)-Pad56)") (class "Default")
      (node (ref "U401") (pin "56") (pinfunction "P1.29(TCK)_56") (pintype "bidirectional"))
    )
    (net (code "89") (name "unconnected-(U401-P1.30(TMS)-Pad52)") (class "Default")
      (node (ref "U401") (pin "52") (pinfunction "P1.30(TMS)_52") (pintype "bidirectional"))
    )
    (net (code "90") (name "unconnected-(U401-P1.31({slash}TRST)-Pad20)") (class "Default")
      (node (ref "U401") (pin "20") (pinfunction "P1.31(/TRST)_20") (pintype "bidirectional"))
    )
    (net (code "91") (name "unconnected-(U401-RTXC2-Pad5)") (class "Default")
      (node (ref "U401") (pin "5") (pinfunction "RTXC2_5") (pintype "output"))
    )
    (net (code "92") (name "unconnected-(U601-CLKOUT-Pad22)") (class "Default")
      (node (ref "U601") (pin "22") (pinfunction "CLKOUT_22") (pintype "bidirectional"))
    )
    (net (code "93") (name "unconnected-(U601-ES_CL-Pad7)") (class "Default")
      (node (ref "U601") (pin "7") (pinfunction "ES_CL_7") (pintype "bidirectional"))
    )
    (net (code "94") (name "unconnected-(U601-ES_DA-Pad6)") (class "Default")
      (node (ref "U601") (pin "6") (pinfunction "ES_DA_6") (pintype "bidirectional"))
    )
    (net (code "95") (name "unconnected-(U701-CD-PadCD1)") (class "Default")
      (node (ref "U701") (pin "CD1") (pinfunction "CD_CD1") (pintype "bidirectional"))
    )
    (net (code "96") (name "unconnected-(U701-NC-Pad1)") (class "Default")
      (node (ref "U701") (pin "1") (pinfunction "NC_1") (pintype "bidirectional"))
    )
    (net (code "97") (name "unconnected-(U701-RSV-Pad8)") (class "Default")
      (node (ref "U701") (pin "8") (pinfunction "RSV_8") (pintype "bidirectional"))
    )
  )
)
